# DM1098EMB_MIPI_CAM.net
KiCad netlist of a schematic drawn in Altium Designer
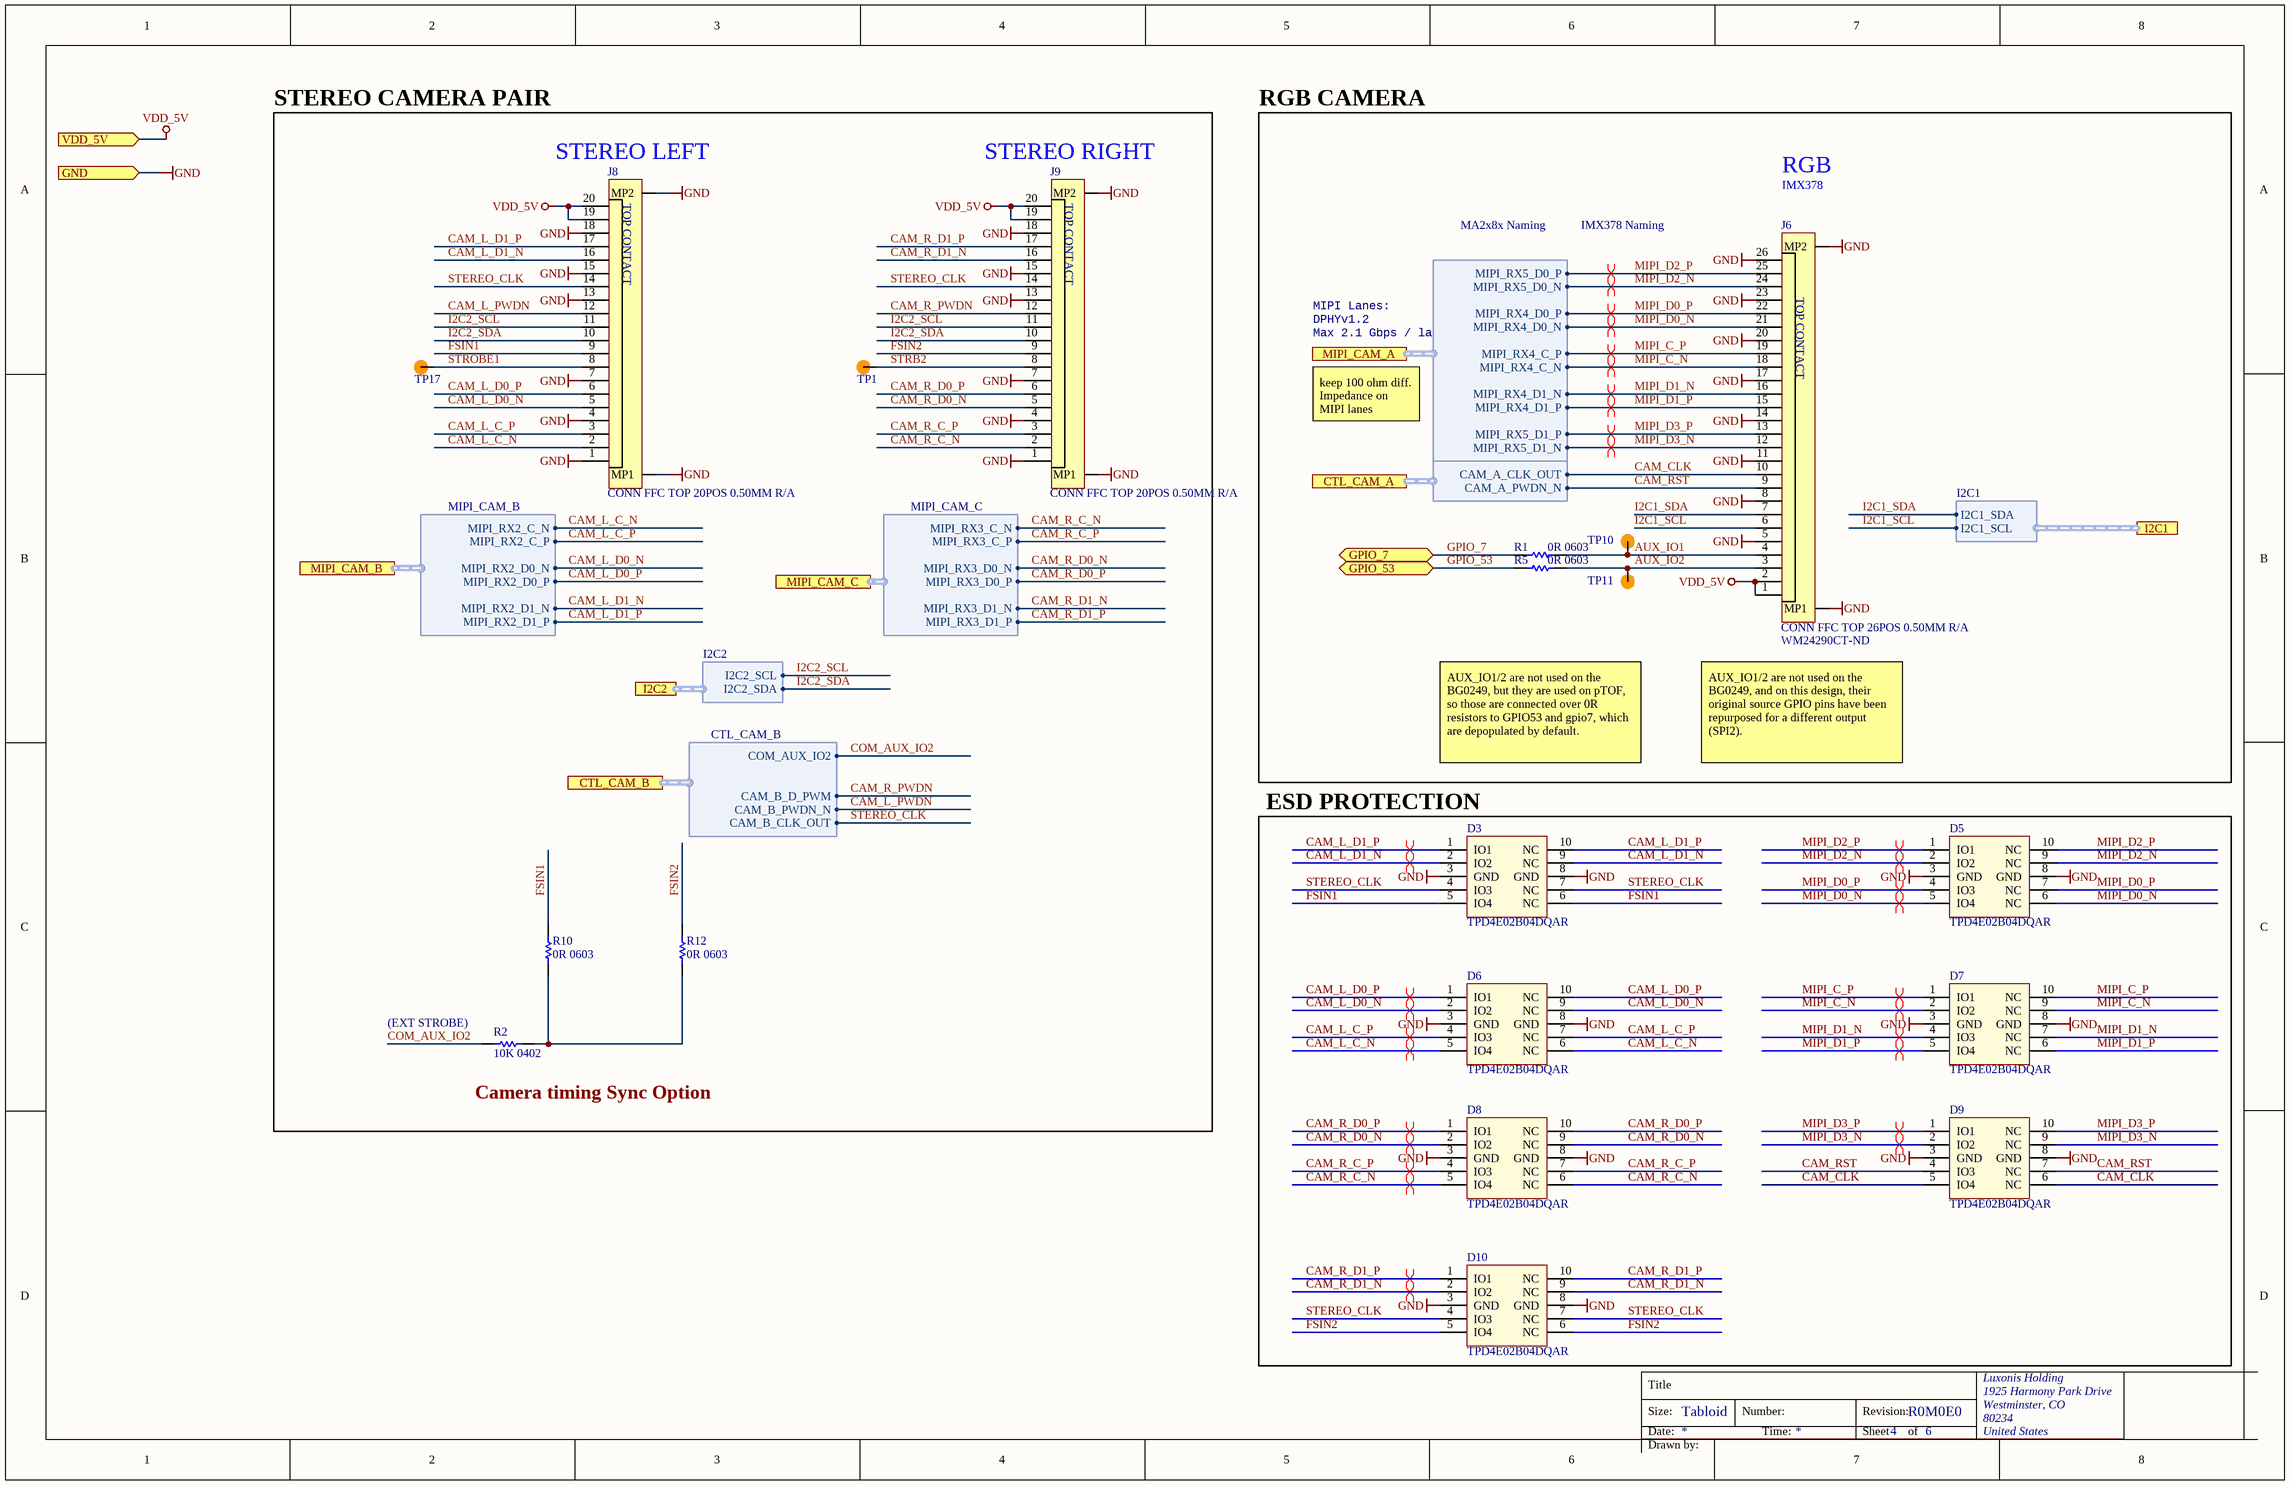
[diagram p0: DM1098EMB_MIPI_CAM.SchDoc]

(export (version "E")
  (design (tool "Eeschema 10.0.6"))
  (components
    (comp (ref "D3")
      (value "TPD4E02B04DQAR")
      (footprint "LuxonisMaster:TPD4E02B04DQAR")
      (libsource (lib "LuxonisMaster") (part "TPD4E02B04DQAR"))
    )
    (comp (ref "D5")
      (value "TPD4E02B04DQAR")
      (footprint "LuxonisMaster:TPD4E02B04DQAR")
      (libsource (lib "LuxonisMaster") (part "TPD4E02B04DQAR"))
    )
    (comp (ref "D6")
      (value "TPD4E02B04DQAR")
      (footprint "LuxonisMaster:TPD4E02B04DQAR")
      (libsource (lib "LuxonisMaster") (part "TPD4E02B04DQAR"))
    )
    (comp (ref "D7")
      (value "TPD4E02B04DQAR")
      (footprint "LuxonisMaster:TPD4E02B04DQAR")
      (libsource (lib "LuxonisMaster") (part "TPD4E02B04DQAR"))
    )
    (comp (ref "D8")
      (value "TPD4E02B04DQAR")
      (footprint "LuxonisMaster:TPD4E02B04DQAR")
      (libsource (lib "LuxonisMaster") (part "TPD4E02B04DQAR"))
    )
    (comp (ref "D9")
      (value "TPD4E02B04DQAR")
      (footprint "LuxonisMaster:TPD4E02B04DQAR")
      (libsource (lib "LuxonisMaster") (part "TPD4E02B04DQAR"))
    )
    (comp (ref "D10")
      (value "TPD4E02B04DQAR")
      (footprint "LuxonisMaster:TPD4E02B04DQAR")
      (libsource (lib "LuxonisMaster") (part "TPD4E02B04DQAR"))
    )
    (comp (ref "J6")
      (value "CONN FFC TOP 26POS 0.50MM R/A")
      (footprint "5052782633")
      (description "0.5 Ffc Zif Btm Cont Embt Pkg 0.5 Fpc Zif Btm FS19")
      (fields (field (name "SUPPLIER PART NUMBER 1") "WM24290CT-ND"))
      (libsource (lib "DM1098FFC") (part "5052782633"))
    )
    (comp (ref "J8")
      (value "CONN FFC TOP 20POS 0.50MM R/A")
      (footprint "5052782033")
      (description "0.5 Ffc Zif Btm Cont Embt Pkg 0.5 Fpc Zif Btm FS19")
      (libsource (lib "DM1098FFC") (part "5052782033"))
    )
    (comp (ref "J9")
      (value "CONN FFC TOP 20POS 0.50MM R/A")
      (footprint "5052782033")
      (description "0.5 Ffc Zif Btm Cont Embt Pkg 0.5 Fpc Zif Btm FS19")
      (libsource (lib "DM1098FFC") (part "5052782033"))
    )
    (comp (ref "R1")
      (value "0R 0603")
      (footprint "RES_Altium_Vault_Generic:RESC0603(1608)_N")
      (fields (field (name "TOLERANCE") "5%"))
      (libsource (lib "LuxonisMaster") (part "CRCW06030000Z0EA"))
    )
    (comp (ref "R2")
      (value "10K 0402")
      (footprint "RES_Altium_Vault_Generic:RESC0402(1005)_N")
      (fields (field (name "TOLERANCE") "1%"))
      (libsource (lib "LuxonisMaster") (part "RC0402FR-1310KL"))
    )
    (comp (ref "R5")
      (value "0R 0603")
      (footprint "RES_Altium_Vault_Generic:RESC0603(1608)_N")
      (fields (field (name "TOLERANCE") "5%"))
      (libsource (lib "LuxonisMaster") (part "CRCW06030000Z0EA"))
    )
    (comp (ref "R10")
      (value "0R 0603")
      (footprint "RES_Altium_Vault_Generic:RESC0603(1608)_N")
      (fields (field (name "TOLERANCE") "5%"))
      (libsource (lib "LuxonisMaster") (part "CRCW06030000Z0EA"))
    )
    (comp (ref "R12")
      (value "0R 0603")
      (footprint "RES_Altium_Vault_Generic:RESC0603(1608)_N")
      (fields (field (name "TOLERANCE") "5%"))
      (libsource (lib "LuxonisMaster") (part "CRCW06030000Z0EA"))
    )
    (comp (ref "TP1")
      (value "TP100_200_NS")
      (footprint "LuxonisMaster:TP100_200_NS")
      (libsource (lib "LuxonisMaster") (part "TEST_POINT"))
    )
    (comp (ref "TP10")
      (value "TP100_200_NS")
      (footprint "LuxonisMaster:TP100_200_NS")
      (libsource (lib "LuxonisMaster") (part "TEST_POINT"))
    )
    (comp (ref "TP11")
      (value "TP100_200_NS")
      (footprint "LuxonisMaster:TP100_200_NS")
      (libsource (lib "LuxonisMaster") (part "TEST_POINT"))
    )
    (comp (ref "TP17")
      (value "TP100_200_NS")
      (footprint "LuxonisMaster:TP100_200_NS")
      (libsource (lib "LuxonisMaster") (part "TEST_POINT"))
    )
  )
  (nets
    (net (code "8") (name "/AUX_IO1") (class "Default")
      (node (ref "J6") (pin "4") (pinfunction "4_4") (pintype "passive"))
      (node (ref "R1") (pin "1") (pinfunction "1_1") (pintype "passive"))
      (node (ref "TP10") (pin "1") (pintype "passive"))
    )
    (net (code "9") (name "/AUX_IO2") (class "Default")
      (node (ref "J6") (pin "3") (pinfunction "3_3") (pintype "passive"))
      (node (ref "R5") (pin "1") (pinfunction "1_1") (pintype "passive"))
      (node (ref "TP11") (pin "1") (pintype "passive"))
    )
    (net (code "10") (name "/CAM_CLK") (class "Default")
      (node (ref "D9") (pin "5") (pinfunction "IO4_5") (pintype "passive"))
      (node (ref "D9") (pin "6") (pinfunction "NC_6") (pintype "passive"))
      (node (ref "J6") (pin "10") (pinfunction "10_10") (pintype "passive"))
    )
    (net (code "11") (name "/CAM_L_C_N") (class "Default")
      (node (ref "D6") (pin "5") (pinfunction "IO4_5") (pintype "passive"))
      (node (ref "D6") (pin "6") (pinfunction "NC_6") (pintype "passive"))
      (node (ref "J8") (pin "2") (pinfunction "2_2") (pintype "passive"))
    )
    (net (code "12") (name "/CAM_L_C_P") (class "Default")
      (node (ref "D6") (pin "4") (pinfunction "IO3_4") (pintype "passive"))
      (node (ref "D6") (pin "7") (pinfunction "NC_7") (pintype "passive"))
      (node (ref "J8") (pin "3") (pinfunction "3_3") (pintype "passive"))
    )
    (net (code "13") (name "/CAM_L_D0_N") (class "Default")
      (node (ref "D6") (pin "2") (pinfunction "IO2_2") (pintype "passive"))
      (node (ref "D6") (pin "9") (pinfunction "NC_9") (pintype "passive"))
      (node (ref "J8") (pin "5") (pinfunction "5_5") (pintype "passive"))
    )
    (net (code "14") (name "/CAM_L_D0_P") (class "Default")
      (node (ref "D6") (pin "1") (pinfunction "IO1_1") (pintype "passive"))
      (node (ref "D6") (pin "10") (pinfunction "NC_10") (pintype "passive"))
      (node (ref "J8") (pin "6") (pinfunction "6_6") (pintype "passive"))
    )
    (net (code "15") (name "/CAM_L_D1_N") (class "Default")
      (node (ref "D3") (pin "2") (pinfunction "IO2_2") (pintype "passive"))
      (node (ref "D3") (pin "9") (pinfunction "NC_9") (pintype "passive"))
      (node (ref "J8") (pin "16") (pinfunction "16_16") (pintype "passive"))
    )
    (net (code "16") (name "/CAM_L_D1_P") (class "Default")
      (node (ref "D3") (pin "1") (pinfunction "IO1_1") (pintype "passive"))
      (node (ref "D3") (pin "10") (pinfunction "NC_10") (pintype "passive"))
      (node (ref "J8") (pin "17") (pinfunction "17_17") (pintype "passive"))
    )
    (net (code "17") (name "/CAM_L_PWDN") (class "Default")
      (node (ref "J8") (pin "12") (pinfunction "12_12") (pintype "passive"))
    )
    (net (code "18") (name "/CAM_RST") (class "Default")
      (node (ref "D9") (pin "4") (pinfunction "IO3_4") (pintype "passive"))
      (node (ref "D9") (pin "7") (pinfunction "NC_7") (pintype "passive"))
      (node (ref "J6") (pin "9") (pinfunction "9_9") (pintype "passive"))
    )
    (net (code "19") (name "/CAM_R_C_N") (class "Default")
      (node (ref "D8") (pin "5") (pinfunction "IO4_5") (pintype "passive"))
      (node (ref "D8") (pin "6") (pinfunction "NC_6") (pintype "passive"))
      (node (ref "J9") (pin "2") (pinfunction "2_2") (pintype "passive"))
    )
    (net (code "20") (name "/CAM_R_C_P") (class "Default")
      (node (ref "D8") (pin "4") (pinfunction "IO3_4") (pintype "passive"))
      (node (ref "D8") (pin "7") (pinfunction "NC_7") (pintype "passive"))
      (node (ref "J9") (pin "3") (pinfunction "3_3") (pintype "passive"))
    )
    (net (code "21") (name "/CAM_R_D0_N") (class "Default")
      (node (ref "D8") (pin "2") (pinfunction "IO2_2") (pintype "passive"))
      (node (ref "D8") (pin "9") (pinfunction "NC_9") (pintype "passive"))
      (node (ref "J9") (pin "5") (pinfunction "5_5") (pintype "passive"))
    )
    (net (code "22") (name "/CAM_R_D0_P") (class "Default")
      (node (ref "D8") (pin "1") (pinfunction "IO1_1") (pintype "passive"))
      (node (ref "D8") (pin "10") (pinfunction "NC_10") (pintype "passive"))
      (node (ref "J9") (pin "6") (pinfunction "6_6") (pintype "passive"))
    )
    (net (code "23") (name "/CAM_R_D1_N") (class "Default")
      (node (ref "D10") (pin "2") (pinfunction "IO2_2") (pintype "passive"))
      (node (ref "D10") (pin "9") (pinfunction "NC_9") (pintype "passive"))
      (node (ref "J9") (pin "16") (pinfunction "16_16") (pintype "passive"))
    )
    (net (code "24") (name "/CAM_R_D1_P") (class "Default")
      (node (ref "D10") (pin "1") (pinfunction "IO1_1") (pintype "passive"))
      (node (ref "D10") (pin "10") (pinfunction "NC_10") (pintype "passive"))
      (node (ref "J9") (pin "17") (pinfunction "17_17") (pintype "passive"))
    )
    (net (code "25") (name "/CAM_R_PWDN") (class "Default")
      (node (ref "J9") (pin "12") (pinfunction "12_12") (pintype "passive"))
    )
    (net (code "26") (name "/COM_AUX_IO2") (class "Default")
      (node (ref "R2") (pin "1") (pinfunction "1_1") (pintype "passive"))
    )
    (net (code "27") (name "/FSIN1") (class "Default")
      (node (ref "D3") (pin "5") (pinfunction "IO4_5") (pintype "passive"))
      (node (ref "D3") (pin "6") (pinfunction "NC_6") (pintype "passive"))
      (node (ref "J8") (pin "9") (pinfunction "9_9") (pintype "passive"))
      (node (ref "R10") (pin "2") (pinfunction "2_2") (pintype "passive"))
    )
    (net (code "28") (name "/FSIN2") (class "Default")
      (node (ref "D10") (pin "5") (pinfunction "IO4_5") (pintype "passive"))
      (node (ref "D10") (pin "6") (pinfunction "NC_6") (pintype "passive"))
      (node (ref "J9") (pin "9") (pinfunction "9_9") (pintype "passive"))
      (node (ref "R12") (pin "2") (pinfunction "2_2") (pintype "passive"))
    )
    (net (code "29") (name "/GPIO_7") (class "Default")
      (node (ref "R1") (pin "2") (pinfunction "2_2") (pintype "passive"))
    )
    (net (code "30") (name "/GPIO_53") (class "Default")
      (node (ref "R5") (pin "2") (pinfunction "2_2") (pintype "passive"))
    )
    (net (code "31") (name "/I2C1_SCL") (class "Default")
      (node (ref "J6") (pin "6") (pinfunction "6_6") (pintype "passive"))
    )
    (net (code "32") (name "/I2C1_SDA") (class "Default")
      (node (ref "J6") (pin "7") (pinfunction "7_7") (pintype "passive"))
    )
    (net (code "33") (name "/I2C2_SCL") (class "Default")
      (node (ref "J8") (pin "11") (pinfunction "11_11") (pintype "passive"))
      (node (ref "J9") (pin "11") (pinfunction "11_11") (pintype "passive"))
    )
    (net (code "34") (name "/I2C2_SDA") (class "Default")
      (node (ref "J8") (pin "10") (pinfunction "10_10") (pintype "passive"))
      (node (ref "J9") (pin "10") (pinfunction "10_10") (pintype "passive"))
    )
    (net (code "35") (name "/MIPI_C_N") (class "Default")
      (node (ref "D7") (pin "2") (pinfunction "IO2_2") (pintype "passive"))
      (node (ref "D7") (pin "9") (pinfunction "NC_9") (pintype "passive"))
      (node (ref "J6") (pin "18") (pinfunction "18_18") (pintype "passive"))
    )
    (net (code "36") (name "/MIPI_C_P") (class "Default")
      (node (ref "D7") (pin "1") (pinfunction "IO1_1") (pintype "passive"))
      (node (ref "D7") (pin "10") (pinfunction "NC_10") (pintype "passive"))
      (node (ref "J6") (pin "19") (pinfunction "19_19") (pintype "passive"))
    )
    (net (code "37") (name "/MIPI_D0_N") (class "Default")
      (node (ref "D5") (pin "5") (pinfunction "IO4_5") (pintype "passive"))
      (node (ref "D5") (pin "6") (pinfunction "NC_6") (pintype "passive"))
      (node (ref "J6") (pin "21") (pinfunction "21_21") (pintype "passive"))
    )
    (net (code "38") (name "/MIPI_D0_P") (class "Default")
      (node (ref "D5") (pin "4") (pinfunction "IO3_4") (pintype "passive"))
      (node (ref "D5") (pin "7") (pinfunction "NC_7") (pintype "passive"))
      (node (ref "J6") (pin "22") (pinfunction "22_22") (pintype "passive"))
    )
    (net (code "39") (name "/MIPI_D1_N") (class "Default")
      (node (ref "D7") (pin "4") (pinfunction "IO3_4") (pintype "passive"))
      (node (ref "D7") (pin "7") (pinfunction "NC_7") (pintype "passive"))
      (node (ref "J6") (pin "16") (pinfunction "16_16") (pintype "passive"))
    )
    (net (code "40") (name "/MIPI_D1_P") (class "Default")
      (node (ref "D7") (pin "5") (pinfunction "IO4_5") (pintype "passive"))
      (node (ref "D7") (pin "6") (pinfunction "NC_6") (pintype "passive"))
      (node (ref "J6") (pin "15") (pinfunction "15_15") (pintype "passive"))
    )
    (net (code "41") (name "/MIPI_D2_N") (class "Default")
      (node (ref "D5") (pin "2") (pinfunction "IO2_2") (pintype "passive"))
      (node (ref "D5") (pin "9") (pinfunction "NC_9") (pintype "passive"))
      (node (ref "J6") (pin "24") (pinfunction "24_24") (pintype "passive"))
    )
    (net (code "42") (name "/MIPI_D2_P") (class "Default")
      (node (ref "D5") (pin "1") (pinfunction "IO1_1") (pintype "passive"))
      (node (ref "D5") (pin "10") (pinfunction "NC_10") (pintype "passive"))
      (node (ref "J6") (pin "25") (pinfunction "25_25") (pintype "passive"))
    )
    (net (code "43") (name "/MIPI_D3_N") (class "Default")
      (node (ref "D9") (pin "2") (pinfunction "IO2_2") (pintype "passive"))
      (node (ref "D9") (pin "9") (pinfunction "NC_9") (pintype "passive"))
      (node (ref "J6") (pin "12") (pinfunction "12_12") (pintype "passive"))
    )
    (net (code "44") (name "/MIPI_D3_P") (class "Default")
      (node (ref "D9") (pin "1") (pinfunction "IO1_1") (pintype "passive"))
      (node (ref "D9") (pin "10") (pinfunction "NC_10") (pintype "passive"))
      (node (ref "J6") (pin "13") (pinfunction "13_13") (pintype "passive"))
    )
    (net (code "45") (name "/STEREO_CLK") (class "Default")
      (node (ref "D10") (pin "4") (pinfunction "IO3_4") (pintype "passive"))
      (node (ref "D10") (pin "7") (pinfunction "NC_7") (pintype "passive"))
      (node (ref "D3") (pin "4") (pinfunction "IO3_4") (pintype "passive"))
      (node (ref "D3") (pin "7") (pinfunction "NC_7") (pintype "passive"))
      (node (ref "J8") (pin "14") (pinfunction "14_14") (pintype "passive"))
      (node (ref "J9") (pin "14") (pinfunction "14_14") (pintype "passive"))
    )
    (net (code "46") (name "/STRB2") (class "Default")
      (node (ref "J9") (pin "8") (pinfunction "8_8") (pintype "passive"))
      (node (ref "TP1") (pin "1") (pintype "passive"))
    )
    (net (code "47") (name "/STROBE1") (class "Default")
      (node (ref "J8") (pin "8") (pinfunction "8_8") (pintype "passive"))
      (node (ref "TP17") (pin "1") (pintype "passive"))
    )
    (net (code "55") (name "GND") (class "Default")
      (node (ref "D10") (pin "3") (pinfunction "GND_3") (pintype "passive"))
      (node (ref "D10") (pin "8") (pinfunction "GND_8") (pintype "passive"))
      (node (ref "D3") (pin "3") (pinfunction "GND_3") (pintype "passive"))
      (node (ref "D3") (pin "8") (pinfunction "GND_8") (pintype "passive"))
      (node (ref "D5") (pin "3") (pinfunction "GND_3") (pintype "passive"))
      (node (ref "D5") (pin "8") (pinfunction "GND_8") (pintype "passive"))
      (node (ref "D6") (pin "3") (pinfunction "GND_3") (pintype "passive"))
      (node (ref "D6") (pin "8") (pinfunction "GND_8") (pintype "passive"))
      (node (ref "D7") (pin "3") (pinfunction "GND_3") (pintype "passive"))
      (node (ref "D7") (pin "8") (pinfunction "GND_8") (pintype "passive"))
      (node (ref "D8") (pin "3") (pinfunction "GND_3") (pintype "passive"))
      (node (ref "D8") (pin "8") (pinfunction "GND_8") (pintype "passive"))
      (node (ref "D9") (pin "3") (pinfunction "GND_3") (pintype "passive"))
      (node (ref "D9") (pin "8") (pinfunction "GND_8") (pintype "passive"))
      (node (ref "J6") (pin "11") (pinfunction "11_11") (pintype "passive"))
      (node (ref "J6") (pin "14") (pinfunction "14_14") (pintype "passive"))
      (node (ref "J6") (pin "17") (pinfunction "17_17") (pintype "passive"))
      (node (ref "J6") (pin "20") (pinfunction "20_20") (pintype "passive"))
      (node (ref "J6") (pin "23") (pinfunction "23_23") (pintype "passive"))
      (node (ref "J6") (pin "26") (pinfunction "26_26") (pintype "passive"))
      (node (ref "J6") (pin "5") (pinfunction "5_5") (pintype "passive"))
      (node (ref "J6") (pin "8") (pinfunction "8_8") (pintype "passive"))
      (node (ref "J6") (pin "MP1") (pinfunction "MP1_MP1") (pintype "passive"))
      (node (ref "J6") (pin "MP2") (pinfunction "MP2_MP2") (pintype "passive"))
      (node (ref "J8") (pin "1") (pinfunction "1_1") (pintype "passive"))
      (node (ref "J8") (pin "13") (pinfunction "13_13") (pintype "passive"))
      (node (ref "J8") (pin "15") (pinfunction "15_15") (pintype "passive"))
      (node (ref "J8") (pin "18") (pinfunction "18_18") (pintype "passive"))
      (node (ref "J8") (pin "4") (pinfunction "4_4") (pintype "passive"))
      (node (ref "J8") (pin "7") (pinfunction "7_7") (pintype "passive"))
      (node (ref "J8") (pin "MP1") (pinfunction "MP1_MP1") (pintype "passive"))
      (node (ref "J8") (pin "MP2") (pinfunction "MP2_MP2") (pintype "passive"))
      (node (ref "J9") (pin "1") (pinfunction "1_1") (pintype "passive"))
      (node (ref "J9") (pin "13") (pinfunction "13_13") (pintype "passive"))
      (node (ref "J9") (pin "15") (pinfunction "15_15") (pintype "passive"))
      (node (ref "J9") (pin "18") (pinfunction "18_18") (pintype "passive"))
      (node (ref "J9") (pin "4") (pinfunction "4_4") (pintype "passive"))
      (node (ref "J9") (pin "7") (pinfunction "7_7") (pintype "passive"))
      (node (ref "J9") (pin "MP1") (pinfunction "MP1_MP1") (pintype "passive"))
      (node (ref "J9") (pin "MP2") (pinfunction "MP2_MP2") (pintype "passive"))
    )
    (net (code "56") (name "Net-(R10-Pad1)") (class "Default")
      (node (ref "R10") (pin "1") (pinfunction "1_1") (pintype "passive"))
      (node (ref "R12") (pin "1") (pinfunction "1_1") (pintype "passive"))
      (node (ref "R2") (pin "2") (pinfunction "2_2") (pintype "passive"))
    )
    (net (code "57") (name "VDD_5V") (class "Default")
      (node (ref "J6") (pin "1") (pinfunction "1_1") (pintype "passive"))
      (node (ref "J6") (pin "2") (pinfunction "2_2") (pintype "passive"))
      (node (ref "J8") (pin "19") (pinfunction "19_19") (pintype "passive"))
      (node (ref "J8") (pin "20") (pinfunction "20_20") (pintype "passive"))
      (node (ref "J9") (pin "19") (pinfunction "19_19") (pintype "passive"))
      (node (ref "J9") (pin "20") (pinfunction "20_20") (pintype "passive"))
    )
  )
)
